# MAX3421E_feather_wing.net
KiCad netlist of a schematic drawn in EAGLE
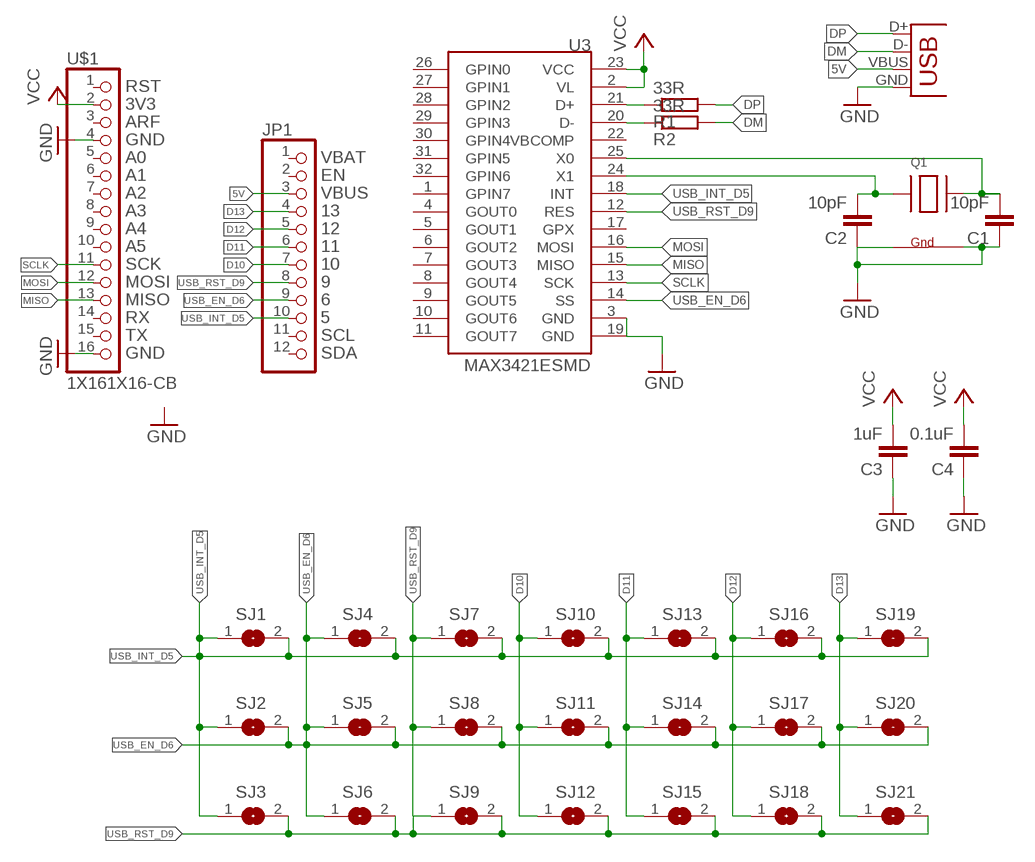
[diagram p0: schematic, sheet 1]

(export (version "E")
  (design (tool "Eeschema 10.0.6"))
  (components
    (comp (ref "C1")
      (value "10pF")
      (footprint "eagle-import:C0805K")
      (libsource (lib "eagle-import") (part "C-EUC0805K"))
    )
    (comp (ref "C2")
      (value "10pF")
      (footprint "eagle-import:C0805K")
      (libsource (lib "eagle-import") (part "C-EUC0805K"))
    )
    (comp (ref "C3")
      (value "1uF")
      (footprint "eagle-import:C0805K")
      (libsource (lib "eagle-import") (part "C-EUC0805K"))
    )
    (comp (ref "C4")
      (value "0.1uF")
      (footprint "eagle-import:C0805K")
      (libsource (lib "eagle-import") (part "C-EUC0805K"))
    )
    (comp (ref "JP1")
      (value "PINHD-1X12-CB")
      (footprint "eagle-import:1X12-CB")
      (libsource (lib "eagle-import") (part "PINHD-1X12-CB"))
    )
    (comp (ref "JP3")
      (value "USBUSB-A-S-NOSILK")
      (footprint "eagle-import:USB-A-S-NOSILK")
      (libsource (lib "eagle-import") (part "USBUSB-A-S-NOSILK"))
    )
    (comp (ref "Q1")
      (value "XTAL-4-3225")
      (footprint "eagle-import:NX3225")
      (libsource (lib "eagle-import") (part "XTAL-4-3225"))
    )
    (comp (ref "R1")
      (value "33R")
      (footprint "eagle-import:R0805")
      (libsource (lib "eagle-import") (part "R-EU_R0805"))
    )
    (comp (ref "R2")
      (value "33R")
      (footprint "eagle-import:R0805")
      (libsource (lib "eagle-import") (part "R-EU_R0805"))
    )
    (comp (ref "SJ1") (value "SJ") (footprint "eagle-import:SJ") (libsource (lib "eagle-import") (part "SJ")))
    (comp (ref "SJ2") (value "SJ") (footprint "eagle-import:SJ") (libsource (lib "eagle-import") (part "SJ")))
    (comp (ref "SJ3") (value "SJ") (footprint "eagle-import:SJ") (libsource (lib "eagle-import") (part "SJ")))
    (comp (ref "SJ4") (value "SJ") (footprint "eagle-import:SJ") (libsource (lib "eagle-import") (part "SJ")))
    (comp (ref "SJ5") (value "SJ") (footprint "eagle-import:SJ") (libsource (lib "eagle-import") (part "SJ")))
    (comp (ref "SJ6") (value "SJ") (footprint "eagle-import:SJ") (libsource (lib "eagle-import") (part "SJ")))
    (comp (ref "SJ7") (value "SJ") (footprint "eagle-import:SJ") (libsource (lib "eagle-import") (part "SJ")))
    (comp (ref "SJ8") (value "SJ") (footprint "eagle-import:SJ") (libsource (lib "eagle-import") (part "SJ")))
    (comp (ref "SJ9") (value "SJ") (footprint "eagle-import:SJ") (libsource (lib "eagle-import") (part "SJ")))
    (comp (ref "SJ10")
      (value "SJ")
      (footprint "eagle-import:SJ")
      (libsource (lib "eagle-import") (part "SJ"))
    )
    (comp (ref "SJ11")
      (value "SJ")
      (footprint "eagle-import:SJ")
      (libsource (lib "eagle-import") (part "SJ"))
    )
    (comp (ref "SJ12")
      (value "SJ")
      (footprint "eagle-import:SJ")
      (libsource (lib "eagle-import") (part "SJ"))
    )
    (comp (ref "SJ13")
      (value "SJ")
      (footprint "eagle-import:SJ")
      (libsource (lib "eagle-import") (part "SJ"))
    )
    (comp (ref "SJ14")
      (value "SJ")
      (footprint "eagle-import:SJ")
      (libsource (lib "eagle-import") (part "SJ"))
    )
    (comp (ref "SJ15")
      (value "SJ")
      (footprint "eagle-import:SJ")
      (libsource (lib "eagle-import") (part "SJ"))
    )
    (comp (ref "SJ16")
      (value "SJ")
      (footprint "eagle-import:SJ")
      (libsource (lib "eagle-import") (part "SJ"))
    )
    (comp (ref "SJ17")
      (value "SJ")
      (footprint "eagle-import:SJ")
      (libsource (lib "eagle-import") (part "SJ"))
    )
    (comp (ref "SJ18")
      (value "SJ")
      (footprint "eagle-import:SJ")
      (libsource (lib "eagle-import") (part "SJ"))
    )
    (comp (ref "SJ19")
      (value "SJ")
      (footprint "eagle-import:SJ")
      (libsource (lib "eagle-import") (part "SJ"))
    )
    (comp (ref "SJ20")
      (value "SJ")
      (footprint "eagle-import:SJ")
      (libsource (lib "eagle-import") (part "SJ"))
    )
    (comp (ref "SJ21")
      (value "SJ")
      (footprint "eagle-import:SJ")
      (libsource (lib "eagle-import") (part "SJ"))
    )
    (comp (ref "U$1")
      (value "1X161X16-CB")
      (footprint "eagle-import:1X16-CB")
      (libsource (lib "eagle-import") (part "1X161X16-CB"))
    )
    (comp (ref "U3")
      (value "MAX3421ESMD")
      (footprint "eagle-import:TQFP32-5MM")
      (libsource (lib "eagle-import") (part "MAX3421ESMD"))
    )
  )
  (nets
    (net (code "1") (name "5V") (class "Default")
      (node (ref "JP1") (pin "3") (pinfunction "3_3") (pintype "passive"))
      (node (ref "JP3") (pin "VBUS") (pinfunction "VBUS_VBUS") (pintype "bidirectional"))
    )
    (net (code "2") (name "D10") (class "Default")
      (node (ref "JP1") (pin "7") (pinfunction "7_7") (pintype "passive"))
      (node (ref "SJ10") (pin "1") (pinfunction "1_1") (pintype "passive"))
      (node (ref "SJ11") (pin "1") (pinfunction "1_1") (pintype "passive"))
      (node (ref "SJ12") (pin "1") (pinfunction "1_1") (pintype "passive"))
    )
    (net (code "3") (name "D11") (class "Default")
      (node (ref "JP1") (pin "6") (pinfunction "6_6") (pintype "passive"))
      (node (ref "SJ13") (pin "1") (pinfunction "1_1") (pintype "passive"))
      (node (ref "SJ14") (pin "1") (pinfunction "1_1") (pintype "passive"))
      (node (ref "SJ15") (pin "1") (pinfunction "1_1") (pintype "passive"))
    )
    (net (code "4") (name "D12") (class "Default")
      (node (ref "JP1") (pin "5") (pinfunction "5_5") (pintype "passive"))
      (node (ref "SJ16") (pin "1") (pinfunction "1_1") (pintype "passive"))
      (node (ref "SJ17") (pin "1") (pinfunction "1_1") (pintype "passive"))
      (node (ref "SJ18") (pin "1") (pinfunction "1_1") (pintype "passive"))
    )
    (net (code "5") (name "D13") (class "Default")
      (node (ref "JP1") (pin "4") (pinfunction "4_4") (pintype "passive"))
      (node (ref "SJ19") (pin "1") (pinfunction "1_1") (pintype "passive"))
      (node (ref "SJ20") (pin "1") (pinfunction "1_1") (pintype "passive"))
      (node (ref "SJ21") (pin "1") (pinfunction "1_1") (pintype "passive"))
    )
    (net (code "6") (name "DM") (class "Default")
      (node (ref "JP3") (pin "D-") (pinfunction "D-_D-") (pintype "bidirectional"))
      (node (ref "R2") (pin "2") (pinfunction "2_2") (pintype "passive"))
    )
    (net (code "7") (name "DP") (class "Default")
      (node (ref "JP3") (pin "D+") (pinfunction "D+_D+") (pintype "bidirectional"))
      (node (ref "R1") (pin "2") (pinfunction "2_2") (pintype "passive"))
    )
    (net (code "8") (name "GND") (class "Default")
      (node (ref "C1") (pin "1") (pinfunction "1_1") (pintype "passive"))
      (node (ref "C2") (pin "1") (pinfunction "1_1") (pintype "passive"))
      (node (ref "C3") (pin "1") (pinfunction "1_1") (pintype "passive"))
      (node (ref "C4") (pin "1") (pinfunction "1_1") (pintype "passive"))
      (node (ref "JP3") (pin "GND") (pinfunction "GND_GND") (pintype "bidirectional"))
      (node (ref "Q1") (pin "2") (pinfunction "G2_2") (pintype "power_in"))
      (node (ref "Q1") (pin "4") (pinfunction "G1_4") (pintype "power_in"))
      (node (ref "U$1") (pin "16") (pinfunction "16_16") (pintype "passive"))
      (node (ref "U$1") (pin "4") (pinfunction "4_4") (pintype "passive"))
      (node (ref "U3") (pin "19") (pinfunction "GND_19") (pintype "bidirectional"))
      (node (ref "U3") (pin "3") (pinfunction "GND_3") (pintype "bidirectional"))
    )
    (net (code "9") (name "MISO") (class "Default")
      (node (ref "U$1") (pin "13") (pinfunction "13_13") (pintype "passive"))
      (node (ref "U3") (pin "15") (pinfunction "MISO_15") (pintype "bidirectional"))
    )
    (net (code "10") (name "MOSI") (class "Default")
      (node (ref "U$1") (pin "12") (pinfunction "12_12") (pintype "passive"))
      (node (ref "U3") (pin "16") (pinfunction "MOSI_16") (pintype "bidirectional"))
    )
    (net (code "11") (name "Net-(Q1-X1)") (class "Default")
      (node (ref "C2") (pin "2") (pinfunction "2_2") (pintype "passive"))
      (node (ref "Q1") (pin "1") (pinfunction "X1_1") (pintype "bidirectional"))
      (node (ref "U3") (pin "24") (pinfunction "X1_24") (pintype "bidirectional"))
    )
    (net (code "12") (name "Net-(Q1-X2)") (class "Default")
      (node (ref "C1") (pin "2") (pinfunction "2_2") (pintype "passive"))
      (node (ref "Q1") (pin "3") (pinfunction "X2_3") (pintype "bidirectional"))
      (node (ref "U3") (pin "25") (pinfunction "X0_25") (pintype "bidirectional"))
    )
    (net (code "13") (name "Net-(U3-D+)") (class "Default")
      (node (ref "R1") (pin "1") (pinfunction "1_1") (pintype "passive"))
      (node (ref "U3") (pin "21") (pinfunction "D+_21") (pintype "bidirectional"))
    )
    (net (code "14") (name "Net-(U3-D-)") (class "Default")
      (node (ref "R2") (pin "1") (pinfunction "1_1") (pintype "passive"))
      (node (ref "U3") (pin "20") (pinfunction "D-_20") (pintype "bidirectional"))
    )
    (net (code "15") (name "SCLK") (class "Default")
      (node (ref "U$1") (pin "11") (pinfunction "11_11") (pintype "passive"))
      (node (ref "U3") (pin "13") (pinfunction "SCK_13") (pintype "bidirectional"))
    )
    (net (code "16") (name "USB_EN_D6") (class "Default")
      (node (ref "JP1") (pin "9") (pinfunction "9_9") (pintype "passive"))
      (node (ref "SJ11") (pin "2") (pinfunction "2_2") (pintype "passive"))
      (node (ref "SJ14") (pin "2") (pinfunction "2_2") (pintype "passive"))
      (node (ref "SJ17") (pin "2") (pinfunction "2_2") (pintype "passive"))
      (node (ref "SJ2") (pin "2") (pinfunction "2_2") (pintype "passive"))
      (node (ref "SJ20") (pin "2") (pinfunction "2_2") (pintype "passive"))
      (node (ref "SJ4") (pin "1") (pinfunction "1_1") (pintype "passive"))
      (node (ref "SJ5") (pin "1") (pinfunction "1_1") (pintype "passive"))
      (node (ref "SJ5") (pin "2") (pinfunction "2_2") (pintype "passive"))
      (node (ref "SJ6") (pin "1") (pinfunction "1_1") (pintype "passive"))
      (node (ref "SJ8") (pin "2") (pinfunction "2_2") (pintype "passive"))
      (node (ref "U3") (pin "14") (pinfunction "SS_14") (pintype "bidirectional"))
    )
    (net (code "17") (name "USB_INT_D5") (class "Default")
      (node (ref "JP1") (pin "10") (pinfunction "10_10") (pintype "passive"))
      (node (ref "SJ1") (pin "1") (pinfunction "1_1") (pintype "passive"))
      (node (ref "SJ1") (pin "2") (pinfunction "2_2") (pintype "passive"))
      (node (ref "SJ10") (pin "2") (pinfunction "2_2") (pintype "passive"))
      (node (ref "SJ13") (pin "2") (pinfunction "2_2") (pintype "passive"))
      (node (ref "SJ16") (pin "2") (pinfunction "2_2") (pintype "passive"))
      (node (ref "SJ19") (pin "2") (pinfunction "2_2") (pintype "passive"))
      (node (ref "SJ2") (pin "1") (pinfunction "1_1") (pintype "passive"))
      (node (ref "SJ3") (pin "1") (pinfunction "1_1") (pintype "passive"))
      (node (ref "SJ4") (pin "2") (pinfunction "2_2") (pintype "passive"))
      (node (ref "SJ7") (pin "2") (pinfunction "2_2") (pintype "passive"))
      (node (ref "U3") (pin "18") (pinfunction "INT_18") (pintype "bidirectional"))
    )
    (net (code "18") (name "USB_RST_D9") (class "Default")
      (node (ref "JP1") (pin "8") (pinfunction "8_8") (pintype "passive"))
      (node (ref "SJ12") (pin "2") (pinfunction "2_2") (pintype "passive"))
      (node (ref "SJ15") (pin "2") (pinfunction "2_2") (pintype "passive"))
      (node (ref "SJ18") (pin "2") (pinfunction "2_2") (pintype "passive"))
      (node (ref "SJ21") (pin "2") (pinfunction "2_2") (pintype "passive"))
      (node (ref "SJ3") (pin "2") (pinfunction "2_2") (pintype "passive"))
      (node (ref "SJ6") (pin "2") (pinfunction "2_2") (pintype "passive"))
      (node (ref "SJ7") (pin "1") (pinfunction "1_1") (pintype "passive"))
      (node (ref "SJ8") (pin "1") (pinfunction "1_1") (pintype "passive"))
      (node (ref "SJ9") (pin "1") (pinfunction "1_1") (pintype "passive"))
      (node (ref "SJ9") (pin "2") (pinfunction "2_2") (pintype "passive"))
      (node (ref "U3") (pin "12") (pinfunction "RES_12") (pintype "bidirectional"))
    )
    (net (code "19") (name "VCC") (class "Default")
      (node (ref "C3") (pin "2") (pinfunction "2_2") (pintype "passive"))
      (node (ref "C4") (pin "2") (pinfunction "2_2") (pintype "passive"))
      (node (ref "U$1") (pin "2") (pinfunction "2_2") (pintype "passive"))
      (node (ref "U3") (pin "2") (pinfunction "VL_2") (pintype "bidirectional"))
      (node (ref "U3") (pin "23") (pinfunction "VCC_23") (pintype "bidirectional"))
    )
    (net (code "20") (name "unconnected-(JP1-Pad1)") (class "Default")
      (node (ref "JP1") (pin "1") (pinfunction "1_1") (pintype "passive"))
    )
    (net (code "21") (name "unconnected-(JP1-Pad2)") (class "Default")
      (node (ref "JP1") (pin "2") (pinfunction "2_2") (pintype "passive"))
    )
    (net (code "22") (name "unconnected-(JP1-Pad11)") (class "Default")
      (node (ref "JP1") (pin "11") (pinfunction "11_11") (pintype "passive"))
    )
    (net (code "23") (name "unconnected-(JP1-Pad12)") (class "Default")
      (node (ref "JP1") (pin "12") (pinfunction "12_12") (pintype "passive"))
    )
    (net (code "24") (name "unconnected-(U$1-Pad1)") (class "Default")
      (node (ref "U$1") (pin "1") (pinfunction "1_1") (pintype "passive"))
    )
    (net (code "25") (name "unconnected-(U$1-Pad3)") (class "Default")
      (node (ref "U$1") (pin "3") (pinfunction "3_3") (pintype "passive"))
    )
    (net (code "26") (name "unconnected-(U$1-Pad5)") (class "Default")
      (node (ref "U$1") (pin "5") (pinfunction "5_5") (pintype "passive"))
    )
    (net (code "27") (name "unconnected-(U$1-Pad6)") (class "Default")
      (node (ref "U$1") (pin "6") (pinfunction "6_6") (pintype "passive"))
    )
    (net (code "28") (name "unconnected-(U$1-Pad7)") (class "Default")
      (node (ref "U$1") (pin "7") (pinfunction "7_7") (pintype "passive"))
    )
    (net (code "29") (name "unconnected-(U$1-Pad8)") (class "Default")
      (node (ref "U$1") (pin "8") (pinfunction "8_8") (pintype "passive"))
    )
    (net (code "30") (name "unconnected-(U$1-Pad9)") (class "Default")
      (node (ref "U$1") (pin "9") (pinfunction "9_9") (pintype "passive"))
    )
    (net (code "31") (name "unconnected-(U$1-Pad10)") (class "Default")
      (node (ref "U$1") (pin "10") (pinfunction "10_10") (pintype "passive"))
    )
    (net (code "32") (name "unconnected-(U$1-Pad14)") (class "Default")
      (node (ref "U$1") (pin "14") (pinfunction "14_14") (pintype "passive"))
    )
    (net (code "33") (name "unconnected-(U$1-Pad15)") (class "Default")
      (node (ref "U$1") (pin "15") (pinfunction "15_15") (pintype "passive"))
    )
    (net (code "34") (name "unconnected-(U3-GOUT0-Pad4)") (class "Default")
      (node (ref "U3") (pin "4") (pinfunction "GOUT0_4") (pintype "bidirectional"))
    )
    (net (code "35") (name "unconnected-(U3-GOUT1-Pad5)") (class "Default")
      (node (ref "U3") (pin "5") (pinfunction "GOUT1_5") (pintype "bidirectional"))
    )
    (net (code "36") (name "unconnected-(U3-GOUT2-Pad6)") (class "Default")
      (node (ref "U3") (pin "6") (pinfunction "GOUT2_6") (pintype "bidirectional"))
    )
    (net (code "37") (name "unconnected-(U3-GOUT3-Pad7)") (class "Default")
      (node (ref "U3") (pin "7") (pinfunction "GOUT3_7") (pintype "bidirectional"))
    )
    (net (code "38") (name "unconnected-(U3-GOUT4-Pad8)") (class "Default")
      (node (ref "U3") (pin "8") (pinfunction "GOUT4_8") (pintype "bidirectional"))
    )
    (net (code "39") (name "unconnected-(U3-GOUT5-Pad9)") (class "Default")
      (node (ref "U3") (pin "9") (pinfunction "GOUT5_9") (pintype "bidirectional"))
    )
    (net (code "40") (name "unconnected-(U3-GOUT6-Pad10)") (class "Default")
      (node (ref "U3") (pin "10") (pinfunction "GOUT6_10") (pintype "bidirectional"))
    )
    (net (code "41") (name "unconnected-(U3-GOUT7-Pad11)") (class "Default")
      (node (ref "U3") (pin "11") (pinfunction "GOUT7_11") (pintype "bidirectional"))
    )
    (net (code "42") (name "unconnected-(U3-GPIN0-Pad26)") (class "Default")
      (node (ref "U3") (pin "26") (pinfunction "GPIN0_26") (pintype "bidirectional"))
    )
    (net (code "43") (name "unconnected-(U3-GPIN1-Pad27)") (class "Default")
      (node (ref "U3") (pin "27") (pinfunction "GPIN1_27") (pintype "bidirectional"))
    )
    (net (code "44") (name "unconnected-(U3-GPIN2-Pad28)") (class "Default")
      (node (ref "U3") (pin "28") (pinfunction "GPIN2_28") (pintype "bidirectional"))
    )
    (net (code "45") (name "unconnected-(U3-GPIN3-Pad29)") (class "Default")
      (node (ref "U3") (pin "29") (pinfunction "GPIN3_29") (pintype "bidirectional"))
    )
    (net (code "46") (name "unconnected-(U3-GPIN4-Pad30)") (class "Default")
      (node (ref "U3") (pin "30") (pinfunction "GPIN4_30") (pintype "bidirectional"))
    )
    (net (code "47") (name "unconnected-(U3-GPIN5-Pad31)") (class "Default")
      (node (ref "U3") (pin "31") (pinfunction "GPIN5_31") (pintype "bidirectional"))
    )
    (net (code "48") (name "unconnected-(U3-GPIN6-Pad32)") (class "Default")
      (node (ref "U3") (pin "32") (pinfunction "GPIN6_32") (pintype "bidirectional"))
    )
    (net (code "49") (name "unconnected-(U3-GPIN7-Pad1)") (class "Default")
      (node (ref "U3") (pin "1") (pinfunction "GPIN7_1") (pintype "bidirectional"))
    )
    (net (code "50") (name "unconnected-(U3-GPX-Pad17)") (class "Default")
      (node (ref "U3") (pin "17") (pinfunction "GPX_17") (pintype "bidirectional"))
    )
    (net (code "51") (name "unconnected-(U3-VBCOMP-Pad22)") (class "Default")
      (node (ref "U3") (pin "22") (pinfunction "VBCOMP_22") (pintype "bidirectional"))
    )
  )
)
